# STM32Ethernet.net
KiCad netlist of a schematic drawn in Altium Designer
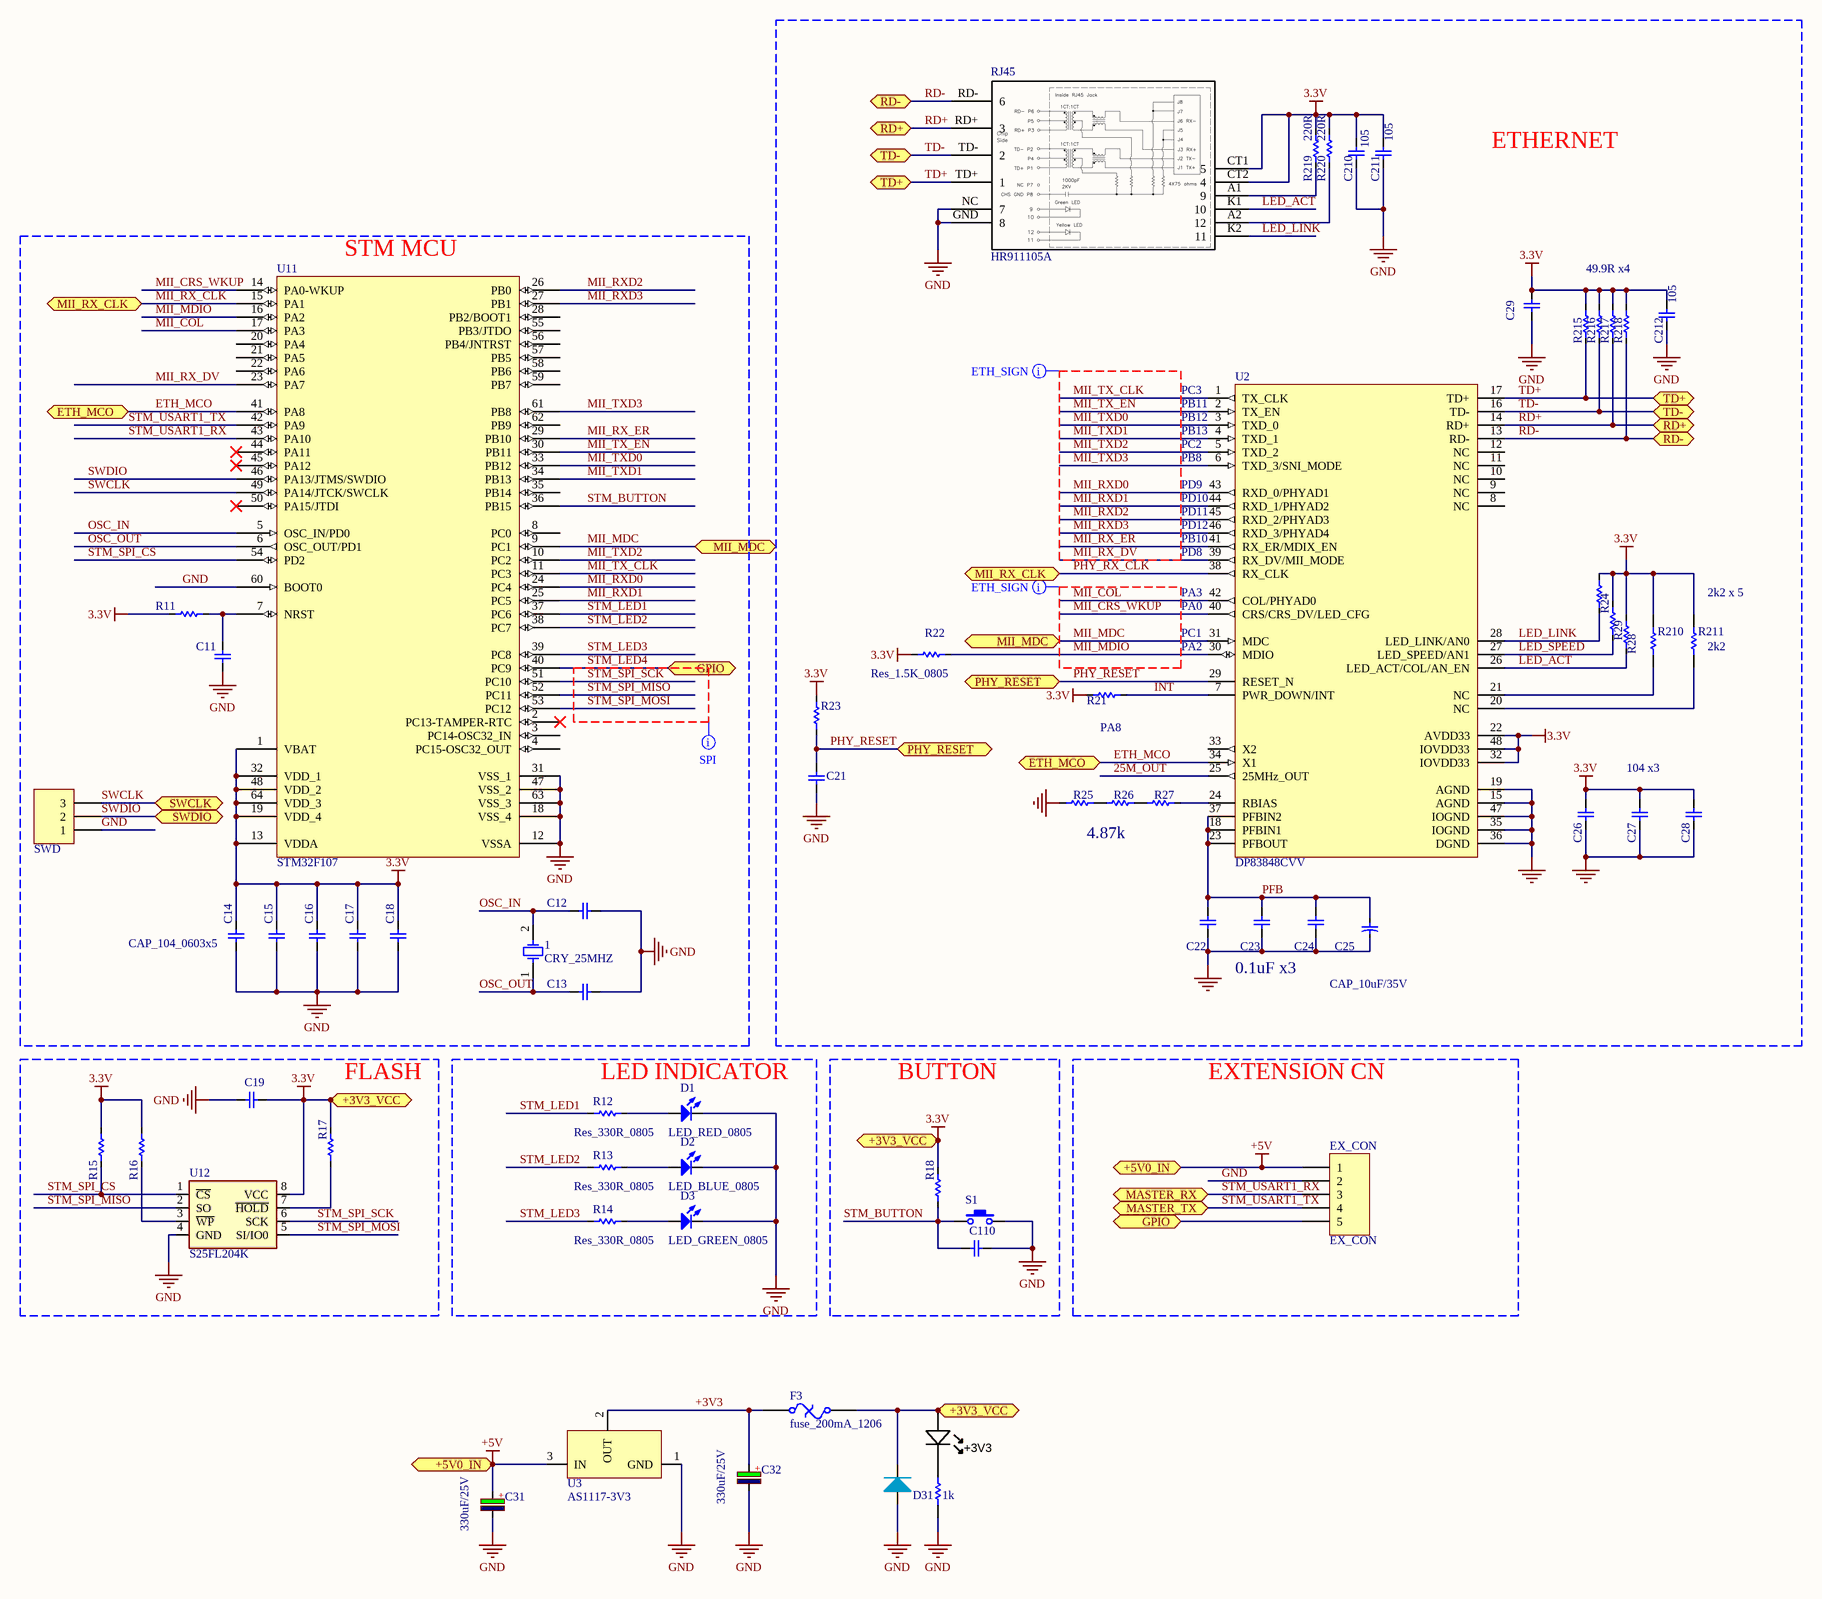
[diagram p0: STM32Ethernet.SchDoc]

(export (version "E")
  (design (tool "Eeschema 10.0.6"))
  (components
    (comp (ref "+3V3")
      (value "Blue")
      (footprint "LED-0805-K")
      (description "LED 0805 SMD Blue 100mcd 470nm")
      (libsource (lib "PBL - Light Sources") (part "LED_SMD_Blue_0805_100mcd"))
    )
    (comp (ref "1")
      (value "CRY_25MHZ")
      (footprint "cry")
      (description "Crystal Oscillator")
      (fields (field (name "PUBLISHER") "Altium Limited"))
      (libsource (lib "THU VIEN CHAN") (part "cry"))
    )
    (comp (ref "C11")
      (value "CAP_102_0603")
      (footprint "CAP_0805_TOP")
      (description "Capacitor")
      (fields (field (name "PUBLISHER") "Altium Limited"))
      (libsource (lib "THU VIEN CHAN") (part "Cap 1206 BUT"))
    )
    (comp (ref "C12")
      (value "CAP_18pF_0603")
      (footprint "CAP_0603_TOP")
      (description "Capacitor")
      (fields (field (name "PUBLISHER") "Altium Limited"))
      (libsource (lib "THU VIEN CHAN") (part "Cap 1206 BUT"))
    )
    (comp (ref "C13")
      (value "CAP_18pF_0603")
      (footprint "CAP_0603_TOP")
      (description "Capacitor")
      (fields (field (name "PUBLISHER") "Altium Limited"))
      (libsource (lib "THU VIEN CHAN") (part "Cap 1206 BUT"))
    )
    (comp (ref "C14")
      (value "CAP_104_0603")
      (footprint "CAPC1608N_F")
      (description "Capacitor")
      (fields (field (name "PUBLISHER") "Altium Limited"))
      (libsource (lib "THU VIEN CHAN") (part "Cap 1206 BUT"))
    )
    (comp (ref "C15")
      (value "CAP_104_0603")
      (footprint "CAPC1608N_F")
      (description "Capacitor")
      (fields (field (name "PUBLISHER") "Altium Limited"))
      (libsource (lib "THU VIEN CHAN") (part "Cap 1206 BUT"))
    )
    (comp (ref "C16")
      (value "CAP_104_0603")
      (footprint "CAPC1608N_F")
      (description "Capacitor")
      (fields (field (name "PUBLISHER") "Altium Limited"))
      (libsource (lib "THU VIEN CHAN") (part "Cap 1206 BUT"))
    )
    (comp (ref "C17")
      (value "CAP_104_0603")
      (footprint "CAPC1608N_F")
      (description "Capacitor")
      (fields (field (name "PUBLISHER") "Altium Limited"))
      (libsource (lib "THU VIEN CHAN") (part "Cap 1206 BUT"))
    )
    (comp (ref "C18")
      (value "CAP_104_0603")
      (footprint "CAPC1608N_F")
      (description "Capacitor")
      (fields (field (name "PUBLISHER") "Altium Limited"))
      (libsource (lib "THU VIEN CHAN") (part "Cap 1206 BUT"))
    )
    (comp (ref "C19")
      (value "CAP_104_0603")
      (footprint "CAP_0805_TOP")
      (description "Capacitor")
      (fields (field (name "PUBLISHER") "Altium Limited"))
      (libsource (lib "THU VIEN CHAN") (part "Cap 1206 BUT"))
    )
    (comp (ref "C21")
      (value "CAP_102_0603")
      (footprint "CAPC1608N_F")
      (description "Capacitor")
      (fields (field (name "PUBLISHER") "Altium Limited"))
      (libsource (lib "THU VIEN CHAN") (part "Cap 1206 BUT"))
    )
    (comp (ref "C22")
      (value "CAP_104_0603")
      (footprint "CAPC1608N_F")
      (description "Capacitor")
      (fields (field (name "PUBLISHER") "Altium Limited"))
      (libsource (lib "THU VIEN CHAN") (part "Cap 1206 BUT"))
    )
    (comp (ref "C23")
      (value "CAP_104_0603")
      (footprint "CAPC1608N_F")
      (description "Capacitor")
      (fields (field (name "PUBLISHER") "Altium Limited"))
      (libsource (lib "THU VIEN CHAN") (part "Cap 1206 BUT"))
    )
    (comp (ref "C24")
      (value "CAP_104_0603")
      (footprint "CAPC1608N_F")
      (description "Capacitor")
      (fields (field (name "PUBLISHER") "Altium Limited"))
      (libsource (lib "THU VIEN CHAN") (part "Cap 1206 BUT"))
    )
    (comp (ref "C25")
      (value "CAP_10uF/35V")
      (footprint "CAP_10uF/35V")
      (fields (field (name "PUBLISHER") "Altium Limited"))
      (libsource (lib "THU VIEN CHAN") (part "CAP P"))
    )
    (comp (ref "C26")
      (value "CAP_104_0603")
      (footprint "CAPC1608N_F")
      (description "Capacitor")
      (fields (field (name "PUBLISHER") "Altium Limited"))
      (libsource (lib "THU VIEN CHAN") (part "Cap 1206 BUT"))
    )
    (comp (ref "C27")
      (value "CAP_104_0603")
      (footprint "CAPC1608N_F")
      (description "Capacitor")
      (fields (field (name "PUBLISHER") "Altium Limited"))
      (libsource (lib "THU VIEN CHAN") (part "Cap 1206 BUT"))
    )
    (comp (ref "C28")
      (value "CAP_104_0603")
      (footprint "CAPC1608N_F")
      (description "Capacitor")
      (fields (field (name "PUBLISHER") "Altium Limited"))
      (libsource (lib "THU VIEN CHAN") (part "Cap 1206 BUT"))
    )
    (comp (ref "C29")
      (value "CAP_104_0603")
      (footprint "CAPC2012N_F")
      (description "Capacitor")
      (fields (field (name "PUBLISHER") "Altium Limited"))
      (libsource (lib "THU VIEN CHAN") (part "Cap 1206 BUT"))
    )
    (comp (ref "C31")
      (value "330uF/25V")
      (footprint "PBL - SMD Packages:CAPMP3528X210N")
      (description "Cap 1000uF/16V - 220uF/50V")
      (libsource (lib "heromap") (part "CP4"))
    )
    (comp (ref "C32")
      (value "330uF/25V")
      (footprint "CAPMP3528X210N")
      (description "Cap 1000uF/16V - 220uF/50V")
      (libsource (lib "heromap") (part "CP4"))
    )
    (comp (ref "C110")
      (value "CAP_102_0603")
      (footprint "CAP_0805_TOP")
      (description "Capacitor")
      (fields (field (name "PUBLISHER") "Altium Limited"))
      (libsource (lib "THU VIEN CHAN") (part "Cap 1206 BUT"))
    )
    (comp (ref "C210")
      (value "105")
      (footprint "CAPC1608N_F")
      (description "Capacitor")
      (fields (field (name "PUBLISHER") "Altium Limited"))
      (libsource (lib "THU VIEN CHAN") (part "Cap 1206 BUT"))
    )
    (comp (ref "C211")
      (value "105")
      (footprint "CAPC1608N_F")
      (description "Capacitor")
      (fields (field (name "PUBLISHER") "Altium Limited"))
      (libsource (lib "THU VIEN CHAN") (part "Cap 1206 BUT"))
    )
    (comp (ref "C212")
      (value "105")
      (footprint "CAPC2012N_F")
      (description "Capacitor")
      (fields (field (name "PUBLISHER") "Altium Limited"))
      (libsource (lib "THU VIEN CHAN") (part "Cap 1206 BUT"))
    )
    (comp (ref "D1")
      (value "LED_RED_0805")
      (footprint "LED 0805 TOP")
      (description "Typical INFRARED GaAs LED")
      (fields (field (name "PUBLISHER") "Altium Limited"))
      (libsource (lib "THU VIEN CHAN v1") (part "LED 0805 TOP"))
    )
    (comp (ref "D2")
      (value "LED_BLUE_0805")
      (footprint "LED 0805 TOP")
      (description "Typical INFRARED GaAs LED")
      (fields (field (name "PUBLISHER") "Altium Limited"))
      (libsource (lib "THU VIEN CHAN v1") (part "LED 0805 TOP"))
    )
    (comp (ref "D3")
      (value "LED_GREEN_0805")
      (footprint "LED 0805 TOP")
      (description "Typical INFRARED GaAs LED")
      (fields (field (name "PUBLISHER") "Altium Limited"))
      (libsource (lib "THU VIEN CHAN v1") (part "LED 0805 TOP"))
    )
    (comp (ref "D31") (value "Diode") (footprint "DO-214AC") (libsource (lib "Tuan") (part "Diode")))
    (comp (ref "EX_CON")
      (value "EX_CON")
      (footprint "HDR1X5")
      (description "Header, 5-Pin")
      (fields (field (name "PUBLISHER") "Altium Limited"))
      (libsource (lib "Miscellaneous Connectors") (part "Header 5"))
    )
    (comp (ref "F3")
      (value "fuse_200mA_1206")
      (footprint "SMD 1206")
      (description "Thermal Fuse")
      (fields (field (name "PUBLISHER") "Altium Limited"))
      (libsource (lib "Miscellaneous Devices") (part "Fuse Thermal"))
    )
    (comp (ref "R11")
      (value "Res_4.7K_0805")
      (footprint "RES_0805_TOP")
      (description "Resistor")
      (fields (field (name "PUBLISHER") "Altium Limited"))
      (libsource (lib "THU VIEN CHAN") (part "Res"))
    )
    (comp (ref "R12")
      (value "Res_330R_0805")
      (footprint "RES_0805_TOP")
      (description "Resistor")
      (fields (field (name "PUBLISHER") "Altium Limited"))
      (libsource (lib "THU VIEN CHAN") (part "Res"))
    )
    (comp (ref "R13")
      (value "Res_330R_0805")
      (footprint "RES_0805_TOP")
      (description "Resistor")
      (fields (field (name "PUBLISHER") "Altium Limited"))
      (libsource (lib "THU VIEN CHAN") (part "Res"))
    )
    (comp (ref "R14")
      (value "Res_330R_0805")
      (footprint "RES_0805_TOP")
      (description "Resistor")
      (fields (field (name "PUBLISHER") "Altium Limited"))
      (libsource (lib "THU VIEN CHAN") (part "Res"))
    )
    (comp (ref "R15")
      (value "Res_4.7K_0805")
      (footprint "RES_0805_TOP")
      (description "Resistor")
      (fields (field (name "PUBLISHER") "Altium Limited"))
      (libsource (lib "THU VIEN CHAN") (part "Res"))
    )
    (comp (ref "R16")
      (value "Res_4.7K_0805")
      (footprint "RES_0805_TOP")
      (description "Resistor")
      (fields (field (name "PUBLISHER") "Altium Limited"))
      (libsource (lib "THU VIEN CHAN") (part "Res"))
    )
    (comp (ref "R17")
      (value "Res_4.7K_0805")
      (footprint "RES_0805_TOP")
      (description "Resistor")
      (fields (field (name "PUBLISHER") "Altium Limited"))
      (libsource (lib "THU VIEN CHAN") (part "Res"))
    )
    (comp (ref "R18")
      (value "Res_4.7K_0805")
      (footprint "RES_0805_TOP")
      (description "Resistor")
      (fields (field (name "PUBLISHER") "Altium Limited"))
      (libsource (lib "THU VIEN CHAN") (part "Res"))
    )
    (comp (ref "R21")
      (value "Res_2.2K_0805")
      (footprint "RESC1608N_F")
      (description "Resistor")
      (fields (field (name "PUBLISHER") "Altium Limited"))
      (libsource (lib "THU VIEN CHAN") (part "Res"))
    )
    (comp (ref "R22")
      (value "Res_1.5K_0805")
      (footprint "RESC1608N_F")
      (description "Resistor")
      (fields (field (name "PUBLISHER") "Altium Limited"))
      (libsource (lib "") (part "Res_1"))
    )
    (comp (ref "R23")
      (value "Res_4.7K_0805")
      (footprint "RESC1608N_F")
      (description "Resistor")
      (fields (field (name "PUBLISHER") "Altium Limited"))
      (libsource (lib "") (part "Res_1"))
    )
    (comp (ref "R24")
      (value "Res_2.2K_0805")
      (footprint "RESC1608N_F")
      (description "Resistor")
      (fields (field (name "PUBLISHER") "Altium Limited"))
      (libsource (lib "THU VIEN CHAN") (part "Res"))
    )
    (comp (ref "R25")
      (value "Res_47R_0805")
      (footprint "RES_0805_TOP")
      (description "Resistor")
      (fields (field (name "PUBLISHER") "Altium Limited"))
      (libsource (lib "THU VIEN CHAN") (part "Res"))
    )
    (comp (ref "R26")
      (value "Res_120R_0805")
      (footprint "RES_0805_TOP")
      (description "Resistor")
      (fields (field (name "PUBLISHER") "Altium Limited"))
      (libsource (lib "THU VIEN CHAN") (part "Res"))
    )
    (comp (ref "R27")
      (value "Res_4.7K_0805")
      (footprint "RES_0805_TOP")
      (description "Resistor")
      (fields (field (name "PUBLISHER") "Altium Limited"))
      (libsource (lib "THU VIEN CHAN") (part "Res"))
    )
    (comp (ref "R28")
      (value "Res_0R_0603")
      (footprint "RESC1608N_F")
      (description "Resistor")
      (fields (field (name "PUBLISHER") "Altium Limited"))
      (libsource (lib "THU VIEN CHAN") (part "Res"))
    )
    (comp (ref "R29")
      (value "Res_0R_0603")
      (footprint "RESC1608N_F")
      (description "Resistor")
      (fields (field (name "PUBLISHER") "Altium Limited"))
      (libsource (lib "THU VIEN CHAN") (part "Res"))
    )
    (comp (ref "R210") (value "2k2") (footprint "RESC1608N_F") (libsource (lib "Tuan") (part "Res")))
    (comp (ref "R211") (value "2k2") (footprint "RESC1608N_F") (libsource (lib "Tuan") (part "Res")))
    (comp (ref "R215")
      (value "Res_49.9R_0805")
      (footprint "RES_0805_TOP")
      (description "Resistor")
      (fields (field (name "PUBLISHER") "Altium Limited"))
      (libsource (lib "THU VIEN CHAN") (part "Res"))
    )
    (comp (ref "R216")
      (value "Res_49.9R_0805")
      (footprint "RES_0805_TOP")
      (description "Resistor")
      (fields (field (name "PUBLISHER") "Altium Limited"))
      (libsource (lib "THU VIEN CHAN") (part "Res"))
    )
    (comp (ref "R217")
      (value "Res_49.9R_0805")
      (footprint "RES_0805_TOP")
      (description "Resistor")
      (fields (field (name "PUBLISHER") "Altium Limited"))
      (libsource (lib "THU VIEN CHAN") (part "Res"))
    )
    (comp (ref "R218")
      (value "Res_49.9R_0805")
      (footprint "RES_0805_TOP")
      (description "Resistor")
      (fields (field (name "PUBLISHER") "Altium Limited"))
      (libsource (lib "THU VIEN CHAN") (part "Res"))
    )
    (comp (ref "R219")
      (value "220R")
      (footprint "RESC1608N_F")
      (description "Resistor")
      (fields (field (name "PUBLISHER") "Altium Limited"))
      (libsource (lib "THU VIEN CHAN") (part "Res"))
    )
    (comp (ref "R220")
      (value "220R")
      (footprint "RESC1608N_F")
      (description "Resistor")
      (fields (field (name "PUBLISHER") "Altium Limited"))
      (libsource (lib "THU VIEN CHAN") (part "Res"))
    )
    (comp (ref "RJ45") (value "HR911105A") (footprint "HR911105A") (libsource (lib "Tuan") (part "RJ45-LED")))
    (comp (ref "Rled")
      (value "1k")
      (footprint "RESC2012N_F")
      (fields (field (name "Comment") "Res_0805_1k"))
      (libsource (lib "Tuan") (part "Res"))
    )
    (comp (ref "S1")
      (value "BUTTON 2P")
      (footprint "Nut nhan 2 chan  dung")
      (description "Switch")
      (fields (field (name "PUBLISHER") "Altium Limited"))
      (libsource (lib "THU VIEN CHAN v1") (part "BUTTON 2P"))
    )
    (comp (ref "SWD")
      (value "Header 3")
      (footprint "heromap:HDR1X3")
      (description "Header, 3-Pin")
      (fields (field (name "PUBLISHER") "Altium Limited"))
      (libsource (lib "heromap") (part "Header 3"))
    )
    (comp (ref "U2")
      (value "DP83848CVV")
      (footprint "LQFP48")
      (libsource (lib "THU VIEN CHAN v1") (part "DP83848CVV"))
    )
    (comp (ref "U3") (value "AS1117-3V3") (footprint "SOT223-4N") (libsource (lib "Tuan") (part "AS1117")))
    (comp (ref "U11")
      (value "STM32F107")
      (footprint "LQFP64_N")
      (description "STM32 ARM-based 32-bit MCU with 128 Kbytes Flash, 64-pin LQFP, Industrial Temperature")
      (fields (field (name "PUBLISHER") "Altium Limited"))
      (libsource (lib "ST Microcontroller 32-Bit STM32") (part "STM32F103RBT6"))
    )
    (comp (ref "U12")
      (value "S25FL204K")
      (footprint "SOIC_8")
      (libsource (lib "THU VIEN CHAN v1") (part "S25FL204K"))
    )
  )
  (nets
    (net (code "1") (name "+5V") (class "Default")
      (node (ref "C31") (pin "1") (pinfunction "1_1") (pintype "passive"))
      (node (ref "EX_CON") (pin "1") (pinfunction "1_1") (pintype "passive"))
      (node (ref "U3") (pin "3") (pinfunction "IN_3") (pintype "power_in"))
    )
    (net (code "2") (name "/+3V3") (class "Default")
      (node (ref "C32") (pin "1") (pinfunction "1_1") (pintype "passive"))
      (node (ref "F3") (pin "1") (pinfunction "1_1") (pintype "passive"))
      (node (ref "U3") (pin "2") (pinfunction "OUT_2") (pintype "power_in"))
    )
    (net (code "3") (name "/25M_OUT") (class "Default")
      (node (ref "U2") (pin "25") (pinfunction "25MHz_OUT_25") (pintype "output"))
    )
    (net (code "4") (name "/ETH_MCO") (class "Default")
      (node (ref "U11") (pin "41") (pinfunction "PA8_41") (pintype "bidirectional"))
      (node (ref "U2") (pin "34") (pinfunction "X1_34") (pintype "input"))
    )
    (net (code "5") (name "/INT") (class "Default")
      (node (ref "R21") (pin "1") (pinfunction "1_1") (pintype "passive"))
      (node (ref "U2") (pin "7") (pinfunction "PWR_DOWN/INT_7") (pintype "passive"))
    )
    (net (code "6") (name "/LED_ACT") (class "Default")
      (node (ref "R28") (pin "2") (pinfunction "2_2") (pintype "passive"))
      (node (ref "RJ45") (pin "K1") (pinfunction "10_K1") (pintype "passive"))
      (node (ref "U2") (pin "26") (pinfunction "LED_ACT/COL/AN_EN_26") (pintype "passive"))
    )
    (net (code "7") (name "/LED_LINK") (class "Default")
      (node (ref "R24") (pin "1") (pinfunction "1_1") (pintype "passive"))
      (node (ref "RJ45") (pin "K2") (pinfunction "11_K2") (pintype "passive"))
      (node (ref "U2") (pin "28") (pinfunction "LED_LINK/AN0_28") (pintype "passive"))
    )
    (net (code "8") (name "/LED_SPEED") (class "Default")
      (node (ref "R29") (pin "1") (pinfunction "1_1") (pintype "passive"))
      (node (ref "U2") (pin "27") (pinfunction "LED_SPEED/AN1_27") (pintype "passive"))
    )
    (net (code "9") (name "/MII_COL") (class "Default")
      (node (ref "U11") (pin "17") (pinfunction "PA3_17") (pintype "bidirectional"))
      (node (ref "U2") (pin "42") (pinfunction "COL/PHYAD0_42") (pintype "output"))
    )
    (net (code "10") (name "/MII_CRS_WKUP") (class "Default")
      (node (ref "U11") (pin "14") (pinfunction "PA0-WKUP_14") (pintype "bidirectional"))
      (node (ref "U2") (pin "40") (pinfunction "CRS/CRS_DV/LED_CFG_40") (pintype "output"))
    )
    (net (code "11") (name "/MII_MDC") (class "Default")
      (node (ref "U11") (pin "9") (pinfunction "PC1_9") (pintype "bidirectional"))
      (node (ref "U2") (pin "31") (pinfunction "MDC_31") (pintype "input"))
    )
    (net (code "12") (name "/MII_MDIO") (class "Default")
      (node (ref "R22") (pin "2") (pinfunction "2_2") (pintype "passive"))
      (node (ref "U11") (pin "16") (pinfunction "PA2_16") (pintype "bidirectional"))
      (node (ref "U2") (pin "30") (pinfunction "MDIO_30") (pintype "bidirectional"))
    )
    (net (code "13") (name "/MII_RXD0") (class "Default")
      (node (ref "U11") (pin "24") (pinfunction "PC4_24") (pintype "bidirectional"))
      (node (ref "U2") (pin "43") (pinfunction "RXD_0/PHYAD1_43") (pintype "output"))
    )
    (net (code "14") (name "/MII_RXD1") (class "Default")
      (node (ref "U11") (pin "25") (pinfunction "PC5_25") (pintype "bidirectional"))
      (node (ref "U2") (pin "44") (pinfunction "RXD_1/PHYAD2_44") (pintype "output"))
    )
    (net (code "15") (name "/MII_RXD2") (class "Default")
      (node (ref "U11") (pin "26") (pinfunction "PB0_26") (pintype "bidirectional"))
      (node (ref "U2") (pin "45") (pinfunction "RXD_2/PHYAD3_45") (pintype "output"))
    )
    (net (code "16") (name "/MII_RXD3") (class "Default")
      (node (ref "U11") (pin "27") (pinfunction "PB1_27") (pintype "bidirectional"))
      (node (ref "U2") (pin "46") (pinfunction "RXD_3/PHYAD4_46") (pintype "output"))
    )
    (net (code "17") (name "/MII_RX_CLK") (class "Default")
      (node (ref "U11") (pin "15") (pinfunction "PA1_15") (pintype "bidirectional"))
      (node (ref "U2") (pin "38") (pinfunction "RX_CLK_38") (pintype "output"))
    )
    (net (code "18") (name "/MII_RX_DV") (class "Default")
      (node (ref "U11") (pin "23") (pinfunction "PA7_23") (pintype "bidirectional"))
      (node (ref "U2") (pin "39") (pinfunction "RX_DV/MII_MODE_39") (pintype "output"))
    )
    (net (code "19") (name "/MII_RX_ER") (class "Default")
      (node (ref "U11") (pin "29") (pinfunction "PB10_29") (pintype "bidirectional"))
      (node (ref "U2") (pin "41") (pinfunction "RX_ER/MDIX_EN_41") (pintype "output"))
    )
    (net (code "20") (name "/MII_TXD0") (class "Default")
      (node (ref "U11") (pin "33") (pinfunction "PB12_33") (pintype "bidirectional"))
      (node (ref "U2") (pin "3") (pinfunction "TXD_0_3") (pintype "input"))
    )
    (net (code "21") (name "/MII_TXD1") (class "Default")
      (node (ref "U11") (pin "34") (pinfunction "PB13_34") (pintype "bidirectional"))
      (node (ref "U2") (pin "4") (pinfunction "TXD_1_4") (pintype "input"))
    )
    (net (code "22") (name "/MII_TXD2") (class "Default")
      (node (ref "U11") (pin "10") (pinfunction "PC2_10") (pintype "bidirectional"))
      (node (ref "U2") (pin "5") (pinfunction "TXD_2_5") (pintype "input"))
    )
    (net (code "23") (name "/MII_TXD3") (class "Default")
      (node (ref "U11") (pin "61") (pinfunction "PB8_61") (pintype "bidirectional"))
      (node (ref "U2") (pin "6") (pinfunction "TXD_3/SNI_MODE_6") (pintype "input"))
    )
    (net (code "24") (name "/MII_TX_CLK") (class "Default")
      (node (ref "U11") (pin "11") (pinfunction "PC3_11") (pintype "bidirectional"))
      (node (ref "U2") (pin "1") (pinfunction "TX_CLK_1") (pintype "output"))
    )
    (net (code "25") (name "/MII_TX_EN") (class "Default")
      (node (ref "U11") (pin "30") (pinfunction "PB11_30") (pintype "bidirectional"))
      (node (ref "U2") (pin "2") (pinfunction "TX_EN_2") (pintype "input"))
    )
    (net (code "26") (name "/OSC_IN") (class "Default")
      (node (ref "1") (pin "2") (pinfunction "OSC2_2") (pintype "passive"))
      (node (ref "C12") (pin "1") (pinfunction "1_1") (pintype "passive"))
      (node (ref "U11") (pin "5") (pinfunction "OSC_IN/PD0_5") (pintype "input"))
    )
    (net (code "27") (name "/OSC_OUT") (class "Default")
      (node (ref "1") (pin "1") (pinfunction "OSC1_1") (pintype "passive"))
      (node (ref "C13") (pin "1") (pinfunction "1_1") (pintype "passive"))
      (node (ref "U11") (pin "6") (pinfunction "OSC_OUT/PD1_6") (pintype "output"))
    )
    (net (code "28") (name "/PFB") (class "Default")
      (node (ref "C22") (pin "2") (pinfunction "2_2") (pintype "passive"))
      (node (ref "C23") (pin "2") (pinfunction "2_2") (pintype "passive"))
      (node (ref "C24") (pin "2") (pinfunction "2_2") (pintype "passive"))
      (node (ref "C25") (pin "1") (pinfunction "1_1") (pintype "passive"))
      (node (ref "U2") (pin "18") (pinfunction "PFBIN1_18") (pintype "passive"))
      (node (ref "U2") (pin "23") (pinfunction "PFBOUT_23") (pintype "passive"))
      (node (ref "U2") (pin "37") (pinfunction "PFBIN2_37") (pintype "passive"))
    )
    (net (code "29") (name "/PHY_RESET") (class "Default")
      (node (ref "C21") (pin "2") (pinfunction "2_2") (pintype "passive"))
      (node (ref "R23") (pin "1") (pinfunction "1_1") (pintype "passive"))
      (node (ref "U2") (pin "29") (pinfunction "RESET_N_29") (pintype "passive"))
    )
    (net (code "30") (name "/RD+") (class "Default")
      (node (ref "R217") (pin "2") (pinfunction "2_2") (pintype "passive"))
      (node (ref "RJ45") (pin "RD+") (pinfunction "3_RD+") (pintype "passive"))
      (node (ref "U2") (pin "14") (pinfunction "RD+_14") (pintype "passive"))
    )
    (net (code "31") (name "/RD-") (class "Default")
      (node (ref "R218") (pin "2") (pinfunction "2_2") (pintype "passive"))
      (node (ref "RJ45") (pin "RD-") (pinfunction "6_RD-") (pintype "passive"))
      (node (ref "U2") (pin "13") (pinfunction "RD-_13") (pintype "passive"))
    )
    (net (code "32") (name "/STM_BUTTON") (class "Default")
      (node (ref "C110") (pin "1") (pinfunction "1_1") (pintype "passive"))
      (node (ref "R18") (pin "2") (pinfunction "2_2") (pintype "passive"))
      (node (ref "S1") (pin "1") (pinfunction "1_1") (pintype "passive"))
      (node (ref "U11") (pin "36") (pinfunction "PB15_36") (pintype "bidirectional"))
    )
    (net (code "33") (name "/STM_LED1") (class "Default")
      (node (ref "R12") (pin "1") (pinfunction "1_1") (pintype "passive"))
      (node (ref "U11") (pin "37") (pinfunction "PC6_37") (pintype "bidirectional"))
    )
    (net (code "34") (name "/STM_LED2") (class "Default")
      (node (ref "R13") (pin "1") (pinfunction "1_1") (pintype "passive"))
      (node (ref "U11") (pin "38") (pinfunction "PC7_38") (pintype "bidirectional"))
    )
    (net (code "35") (name "/STM_LED3") (class "Default")
      (node (ref "R14") (pin "1") (pinfunction "1_1") (pintype "passive"))
      (node (ref "U11") (pin "39") (pinfunction "PC8_39") (pintype "bidirectional"))
    )
    (net (code "36") (name "/STM_LED4") (class "Default")
      (node (ref "EX_CON") (pin "5") (pinfunction "5_5") (pintype "passive"))
      (node (ref "U11") (pin "40") (pinfunction "PC9_40") (pintype "bidirectional"))
    )
    (net (code "37") (name "/STM_SPI_CS") (class "Default")
      (node (ref "R15") (pin "2") (pinfunction "2_2") (pintype "passive"))
      (node (ref "U11") (pin "54") (pinfunction "PD2_54") (pintype "bidirectional"))
      (node (ref "U12") (pin "1") (pinfunction "~{CS}_1") (pintype "passive"))
    )
    (net (code "38") (name "/STM_SPI_MISO") (class "Default")
      (node (ref "U11") (pin "52") (pinfunction "PC11_52") (pintype "bidirectional"))
      (node (ref "U12") (pin "2") (pinfunction "SO_2") (pintype "passive"))
    )
    (net (code "39") (name "/STM_SPI_MOSI") (class "Default")
      (node (ref "U11") (pin "53") (pinfunction "PC12_53") (pintype "bidirectional"))
      (node (ref "U12") (pin "5") (pinfunction "SI/IO0_5") (pintype "passive"))
    )
    (net (code "40") (name "/STM_SPI_SCK") (class "Default")
      (node (ref "U11") (pin "51") (pinfunction "PC10_51") (pintype "bidirectional"))
      (node (ref "U12") (pin "6") (pinfunction "SCK_6") (pintype "passive"))
    )
    (net (code "41") (name "/STM_USART1_RX") (class "Default")
      (node (ref "EX_CON") (pin "3") (pinfunction "3_3") (pintype "passive"))
      (node (ref "U11") (pin "43") (pinfunction "PA10_43") (pintype "bidirectional"))
    )
    (net (code "42") (name "/STM_USART1_TX") (class "Default")
      (node (ref "EX_CON") (pin "4") (pinfunction "4_4") (pintype "passive"))
      (node (ref "U11") (pin "42") (pinfunction "PA9_42") (pintype "bidirectional"))
    )
    (net (code "43") (name "/SWCLK") (class "Default")
      (node (ref "SWD") (pin "3") (pinfunction "3_3") (pintype "passive"))
      (node (ref "U11") (pin "49") (pinfunction "PA14/JTCK/SWCLK_49") (pintype "bidirectional"))
    )
    (net (code "44") (name "/SWDIO") (class "Default")
      (node (ref "SWD") (pin "2") (pinfunction "2_2") (pintype "passive"))
      (node (ref "U11") (pin "46") (pinfunction "PA13/JTMS/SWDIO_46") (pintype "bidirectional"))
    )
    (net (code "45") (name "/TD+") (class "Default")
      (node (ref "R215") (pin "2") (pinfunction "2_2") (pintype "passive"))
      (node (ref "RJ45") (pin "TD+") (pinfunction "1_TD+") (pintype "passive"))
      (node (ref "U2") (pin "17") (pinfunction "TD+_17") (pintype "passive"))
    )
    (net (code "46") (name "/TD-") (class "Default")
      (node (ref "R216") (pin "2") (pinfunction "2_2") (pintype "passive"))
      (node (ref "RJ45") (pin "TD-") (pinfunction "2_TD-") (pintype "passive"))
      (node (ref "U2") (pin "16") (pinfunction "TD-_16") (pintype "passive"))
    )
    (net (code "47") (name "3.3V") (class "Default")
      (node (ref "+3V3") (pin "A") (pinfunction "A_A") (pintype "passive"))
      (node (ref "C14") (pin "1") (pinfunction "1_1") (pintype "passive"))
      (node (ref "C15") (pin "1") (pinfunction "1_1") (pintype "passive"))
      (node (ref "C16") (pin "1") (pinfunction "1_1") (pintype "passive"))
      (node (ref "C17") (pin "1") (pinfunction "1_1") (pintype "passive"))
      (node (ref "C18") (pin "1") (pinfunction "1_1") (pintype "passive"))
      (node (ref "C19") (pin "1") (pinfunction "1_1") (pintype "passive"))
      (node (ref "C210") (pin "1") (pinfunction "1_1") (pintype "passive"))
      (node (ref "C211") (pin "1") (pinfunction "1_1") (pintype "passive"))
      (node (ref "C212") (pin "1") (pinfunction "1_1") (pintype "passive"))
      (node (ref "C26") (pin "2") (pinfunction "2_2") (pintype "passive"))
      (node (ref "C27") (pin "1") (pinfunction "1_1") (pintype "passive"))
      (node (ref "C28") (pin "2") (pinfunction "2_2") (pintype "passive"))
      (node (ref "C29") (pin "1") (pinfunction "1_1") (pintype "passive"))
      (node (ref "D31") (pin "2") (pinfunction "K_2") (pintype "passive"))
      (node (ref "F3") (pin "2") (pinfunction "2_2") (pintype "passive"))
      (node (ref "R11") (pin "2") (pinfunction "2_2") (pintype "passive"))
      (node (ref "R15") (pin "1") (pinfunction "1_1") (pintype "passive"))
      (node (ref "R16") (pin "1") (pinfunction "1_1") (pintype "passive"))
      (node (ref "R17") (pin "1") (pinfunction "1_1") (pintype "passive"))
      (node (ref "R18") (pin "1") (pinfunction "1_1") (pintype "passive"))
      (node (ref "R21") (pin "2") (pinfunction "2_2") (pintype "passive"))
      (node (ref "R210") (pin "2") (pinfunction "2_2") (pintype "passive"))
      (node (ref "R211") (pin "2") (pinfunction "2_2") (pintype "passive"))
      (node (ref "R215") (pin "1") (pinfunction "1_1") (pintype "passive"))
      (node (ref "R216") (pin "1") (pinfunction "1_1") (pintype "passive"))
      (node (ref "R217") (pin "1") (pinfunction "1_1") (pintype "passive"))
      (node (ref "R218") (pin "1") (pinfunction "1_1") (pintype "passive"))
      (node (ref "R219") (pin "1") (pinfunction "1_1") (pintype "passive"))
      (node (ref "R22") (pin "1") (pinfunction "1_1") (pintype "passive"))
      (node (ref "R220") (pin "1") (pinfunction "1_1") (pintype "passive"))
      (node (ref "R23") (pin "2") (pinfunction "2_2") (pintype "passive"))
      (node (ref "R24") (pin "2") (pinfunction "2_2") (pintype "passive"))
      (node (ref "R28") (pin "1") (pinfunction "1_1") (pintype "passive"))
      (node (ref "R29") (pin "2") (pinfunction "2_2") (pintype "passive"))
      (node (ref "RJ45") (pin "CT1") (pinfunction "5_CT1") (pintype "passive"))
      (node (ref "RJ45") (pin "CT2") (pinfunction "4_CT2") (pintype "passive"))
      (node (ref "U11") (pin "1") (pinfunction "VBAT_1") (pintype "power_in"))
      (node (ref "U11") (pin "13") (pinfunction "VDDA_13") (pintype "power_in"))
      (node (ref "U11") (pin "19") (pinfunction "VDD_4_19") (pintype "power_in"))
      (node (ref "U11") (pin "32") (pinfunction "VDD_1_32") (pintype "power_in"))
      (node (ref "U11") (pin "48") (pinfunction "VDD_2_48") (pintype "power_in"))
      (node (ref "U11") (pin "64") (pinfunction "VDD_3_64") (pintype "power_in"))
      (node (ref "U12") (pin "8") (pinfunction "VCC_8") (pintype "passive"))
      (node (ref "U2") (pin "22") (pinfunction "AVDD33_22") (pintype "passive"))
      (node (ref "U2") (pin "32") (pinfunction "IOVDD33_32") (pintype "passive"))
      (node (ref "U2") (pin "48") (pinfunction "IOVDD33_48") (pintype "passive"))
    )
    (net (code "48") (name "GND") (class "Default")
      (node (ref "C11") (pin "2") (pinfunction "2_2") (pintype "passive"))
      (node (ref "C110") (pin "2") (pinfunction "2_2") (pintype "passive"))
      (node (ref "C12") (pin "2") (pinfunction "2_2") (pintype "passive"))
      (node (ref "C13") (pin "2") (pinfunction "2_2") (pintype "passive"))
      (node (ref "C14") (pin "2") (pinfunction "2_2") (pintype "passive"))
      (node (ref "C15") (pin "2") (pinfunction "2_2") (pintype "passive"))
      (node (ref "C16") (pin "2") (pinfunction "2_2") (pintype "passive"))
      (node (ref "C17") (pin "2") (pinfunction "2_2") (pintype "passive"))
      (node (ref "C18") (pin "2") (pinfunction "2_2") (pintype "passive"))
      (node (ref "C19") (pin "2") (pinfunction "2_2") (pintype "passive"))
      (node (ref "C21") (pin "1") (pinfunction "1_1") (pintype "passive"))
      (node (ref "C210") (pin "2") (pinfunction "2_2") (pintype "passive"))
      (node (ref "C211") (pin "2") (pinfunction "2_2") (pintype "passive"))
      (node (ref "C212") (pin "2") (pinfunction "2_2") (pintype "passive"))
      (node (ref "C22") (pin "1") (pinfunction "1_1") (pintype "passive"))
      (node (ref "C23") (pin "1") (pinfunction "1_1") (pintype "passive"))
      (node (ref "C24") (pin "1") (pinfunction "1_1") (pintype "passive"))
      (node (ref "C25") (pin "2") (pinfunction "2_2") (pintype "passive"))
      (node (ref "C26") (pin "1") (pinfunction "1_1") (pintype "passive"))
      (node (ref "C27") (pin "2") (pinfunction "2_2") (pintype "passive"))
      (node (ref "C28") (pin "1") (pinfunction "1_1") (pintype "passive"))
      (node (ref "C29") (pin "2") (pinfunction "2_2") (pintype "passive"))
      (node (ref "C31") (pin "2") (pinfunction "2_2") (pintype "passive"))
      (node (ref "C32") (pin "2") (pinfunction "2_2") (pintype "passive"))
      (node (ref "D1") (pin "2") (pinfunction "K_2") (pintype "passive"))
      (node (ref "D2") (pin "2") (pinfunction "K_2") (pintype "passive"))
      (node (ref "D3") (pin "2") (pinfunction "K_2") (pintype "passive"))
      (node (ref "D31") (pin "1") (pinfunction "A_1") (pintype "passive"))
      (node (ref "EX_CON") (pin "2") (pinfunction "2_2") (pintype "passive"))
      (node (ref "R25") (pin "2") (pinfunction "2_2") (pintype "passive"))
      (node (ref "RJ45") (pin "GND") (pinfunction "8_GND") (pintype "passive"))
      (node (ref "RJ45") (pin "NC") (pinfunction "7_NC") (pintype "passive"))
      (node (ref "Rled") (pin "2") (pinfunction "2_2") (pintype "passive"))
      (node (ref "S1") (pin "2") (pinfunction "2_2") (pintype "passive"))
      (node (ref "SWD") (pin "1") (pinfunction "1_1") (pintype "passive"))
      (node (ref "U11") (pin "12") (pinfunction "VSSA_12") (pintype "power_in"))
      (node (ref "U11") (pin "18") (pinfunction "VSS_4_18") (pintype "power_in"))
      (node (ref "U11") (pin "31") (pinfunction "VSS_1_31") (pintype "power_in"))
      (node (ref "U11") (pin "47") (pinfunction "VSS_2_47") (pintype "power_in"))
      (node (ref "U11") (pin "60") (pinfunction "BOOT0_60") (pintype "input"))
      (node (ref "U11") (pin "63") (pinfunction "VSS_3_63") (pintype "power_in"))
      (node (ref "U12") (pin "4") (pinfunction "GND_4") (pintype "passive"))
      (node (ref "U2") (pin "15") (pinfunction "AGND_15") (pintype "passive"))
      (node (ref "U2") (pin "19") (pinfunction "AGND_19") (pintype "passive"))
      (node (ref "U2") (pin "35") (pinfunction "IOGND_35") (pintype "passive"))
      (node (ref "U2") (pin "36") (pinfunction "DGND_36") (pintype "passive"))
      (node (ref "U2") (pin "47") (pinfunction "IOGND_47") (pintype "passive"))
      (node (ref "U3") (pin "1") (pinfunction "GND_1") (pintype "power_in"))
    )
    (net (code "49") (name "Net-(+3V3-PadK)") (class "Default")
      (node (ref "+3V3") (pin "K") (pinfunction "K_K") (pintype "passive"))
      (node (ref "Rled") (pin "1") (pinfunction "1_1") (pintype "passive"))
    )
    (net (code "50") (name "Net-(D1-A)") (class "Default")
      (node (ref "D1") (pin "1") (pinfunction "A_1") (pintype "passive"))
      (node (ref "R12") (pin "2") (pinfunction "2_2") (pintype "passive"))
    )
    (net (code "51") (name "Net-(D2-A)") (class "Default")
      (node (ref "D2") (pin "1") (pinfunction "A_1") (pintype "passive"))
      (node (ref "R13") (pin "2") (pinfunction "2_2") (pintype "passive"))
    )
    (net (code "52") (name "Net-(D3-A)") (class "Default")
      (node (ref "D3") (pin "1") (pinfunction "A_1") (pintype "passive"))
      (node (ref "R14") (pin "2") (pinfunction "2_2") (pintype "passive"))
    )
    (net (code "53") (name "Net-(R25-Pad1)") (class "Default")
      (node (ref "R25") (pin "1") (pinfunction "1_1") (pintype "passive"))
      (node (ref "R26") (pin "1") (pinfunction "1_1") (pintype "passive"))
    )
    (net (code "54") (name "Net-(R26-Pad2)") (class "Default")
      (node (ref "R26") (pin "2") (pinfunction "2_2") (pintype "passive"))
      (node (ref "R27") (pin "2") (pinfunction "2_2") (pintype "passive"))
    )
    (net (code "55") (name "Net-(R210-Pad1)") (class "Default")
      (node (ref "R210") (pin "1") (pinfunction "1_1") (pintype "passive"))
      (node (ref "U2") (pin "21") (pinfunction "NC_21") (pintype "passive"))
    )
    (net (code "56") (name "Net-(R211-Pad1)") (class "Default")
      (node (ref "R211") (pin "1") (pinfunction "1_1") (pintype "passive"))
      (node (ref "U2") (pin "20") (pinfunction "NC_20") (pintype "passive"))
    )
    (net (code "57") (name "Net-(RJ45-9)") (class "Default")
      (node (ref "R219") (pin "2") (pinfunction "2_2") (pintype "passive"))
      (node (ref "RJ45") (pin "A1") (pinfunction "9_A1") (pintype "passive"))
    )
    (net (code "58") (name "Net-(RJ45-12)") (class "Default")
      (node (ref "R220") (pin "2") (pinfunction "2_2") (pintype "passive"))
      (node (ref "RJ45") (pin "A2") (pinfunction "12_A2") (pintype "passive"))
    )
    (net (code "59") (name "Net-(U2-RBIAS)") (class "Default")
      (node (ref "R27") (pin "1") (pinfunction "1_1") (pintype "passive"))
      (node (ref "U2") (pin "24") (pinfunction "RBIAS_24") (pintype "passive"))
    )
    (net (code "60") (name "Net-(U11-NRST)") (class "Default")
      (node (ref "C11") (pin "1") (pinfunction "1_1") (pintype "passive"))
      (node (ref "R11") (pin "1") (pinfunction "1_1") (pintype "passive"))
      (node (ref "U11") (pin "7") (pinfunction "NRST_7") (pintype "bidirectional"))
    )
    (net (code "61") (name "Net-(U12-~{HOLD})") (class "Default")
      (node (ref "R17") (pin "2") (pinfunction "2_2") (pintype "passive"))
      (node (ref "U12") (pin "7") (pinfunction "~{HOLD}_7") (pintype "passive"))
    )
    (net (code "62") (name "Net-(U12-~{WP})") (class "Default")
      (node (ref "R16") (pin "2") (pinfunction "2_2") (pintype "passive"))
      (node (ref "U12") (pin "3") (pinfunction "~{WP}_3") (pintype "passive"))
    )
    (net (code "63") (name "unconnected-(U2-NC-Pad8)") (class "Default")
      (node (ref "U2") (pin "8") (pinfunction "NC_8") (pintype "passive"))
    )
    (net (code "64") (name "unconnected-(U2-NC-Pad9)") (class "Default")
      (node (ref "U2") (pin "9") (pinfunction "NC_9") (pintype "passive"))
    )
    (net (code "65") (name "unconnected-(U2-NC-Pad10)") (class "Default")
      (node (ref "U2") (pin "10") (pinfunction "NC_10") (pintype "passive"))
    )
    (net (code "66") (name "unconnected-(U2-NC-Pad11)") (class "Default")
      (node (ref "U2") (pin "11") (pinfunction "NC_11") (pintype "passive"))
    )
    (net (code "67") (name "unconnected-(U2-NC-Pad12)") (class "Default")
      (node (ref "U2") (pin "12") (pinfunction "NC_12") (pintype "passive"))
    )
    (net (code "68") (name "unconnected-(U2-X2-Pad33)") (class "Default")
      (node (ref "U2") (pin "33") (pinfunction "X2_33") (pintype "output"))
    )
    (net (code "69") (name "unconnected-(U11-PA4-Pad20)") (class "Default")
      (node (ref "U11") (pin "20") (pinfunction "PA4_20") (pintype "bidirectional"))
    )
    (net (code "70") (name "unconnected-(U11-PA5-Pad21)") (class "Default")
      (node (ref "U11") (pin "21") (pinfunction "PA5_21") (pintype "bidirectional"))
    )
    (net (code "71") (name "unconnected-(U11-PA6-Pad22)") (class "Default")
      (node (ref "U11") (pin "22") (pinfunction "PA6_22") (pintype "bidirectional"))
    )
    (net (code "72") (name "unconnected-(U11-PA11-Pad44)") (class "Default")
      (node (ref "U11") (pin "44") (pinfunction "PA11_44") (pintype "bidirectional+no_connect"))
    )
    (net (code "73") (name "unconnected-(U11-PA12-Pad45)") (class "Default")
      (node (ref "U11") (pin "45") (pinfunction "PA12_45") (pintype "bidirectional+no_connect"))
    )
    (net (code "74") (name "unconnected-(U11-PA15{slash}JTDI-Pad50)") (class "Default")
      (node (ref "U11") (pin "50") (pinfunction "PA15/JTDI_50") (pintype "bidirectional+no_connect"))
    )
    (net (code "75") (name "unconnected-(U11-PB2{slash}BOOT1-Pad28)") (class "Default")
      (node (ref "U11") (pin "28") (pinfunction "PB2/BOOT1_28") (pintype "bidirectional"))
    )
    (net (code "76") (name "unconnected-(U11-PB3{slash}JTDO-Pad55)") (class "Default")
      (node (ref "U11") (pin "55") (pinfunction "PB3/JTDO_55") (pintype "bidirectional"))
    )
    (net (code "77") (name "unconnected-(U11-PB4{slash}JNTRST-Pad56)") (class "Default")
      (node (ref "U11") (pin "56") (pinfunction "PB4/JNTRST_56") (pintype "bidirectional"))
    )
    (net (code "78") (name "unconnected-(U11-PB5-Pad57)") (class "Default")
      (node (ref "U11") (pin "57") (pinfunction "PB5_57") (pintype "bidirectional"))
    )
    (net (code "79") (name "unconnected-(U11-PB6-Pad58)") (class "Default")
      (node (ref "U11") (pin "58") (pinfunction "PB6_58") (pintype "bidirectional"))
    )
    (net (code "80") (name "unconnected-(U11-PB7-Pad59)") (class "Default")
      (node (ref "U11") (pin "59") (pinfunction "PB7_59") (pintype "bidirectional"))
    )
    (net (code "81") (name "unconnected-(U11-PB9-Pad62)") (class "Default")
      (node (ref "U11") (pin "62") (pinfunction "PB9_62") (pintype "bidirectional"))
    )
    (net (code "82") (name "unconnected-(U11-PB14-Pad35)") (class "Default")
      (node (ref "U11") (pin "35") (pinfunction "PB14_35") (pintype "bidirectional"))
    )
    (net (code "83") (name "unconnected-(U11-PC0-Pad8)") (class "Default")
      (node (ref "U11") (pin "8") (pinfunction "PC0_8") (pintype "bidirectional"))
    )
    (net (code "84") (name "unconnected-(U11-PC13-TAMPER-RTC-Pad2)") (class "Default")
      (node (ref "U11") (pin "2") (pinfunction "PC13-TAMPER-RTC_2") (pintype "bidirectional+no_connect"))
    )
    (net (code "85") (name "unconnected-(U11-PC14-OSC32_IN-Pad3)") (class "Default")
      (node (ref "U11") (pin "3") (pinfunction "PC14-OSC32_IN_3") (pintype "bidirectional"))
    )
    (net (code "86") (name "unconnected-(U11-PC15-OSC32_OUT-Pad4)") (class "Default")
      (node (ref "U11") (pin "4") (pinfunction "PC15-OSC32_OUT_4") (pintype "bidirectional"))
    )
  )
)
